# OR_Gate_Using_Transistor.net
KiCad netlist of a schematic drawn in EAGLE
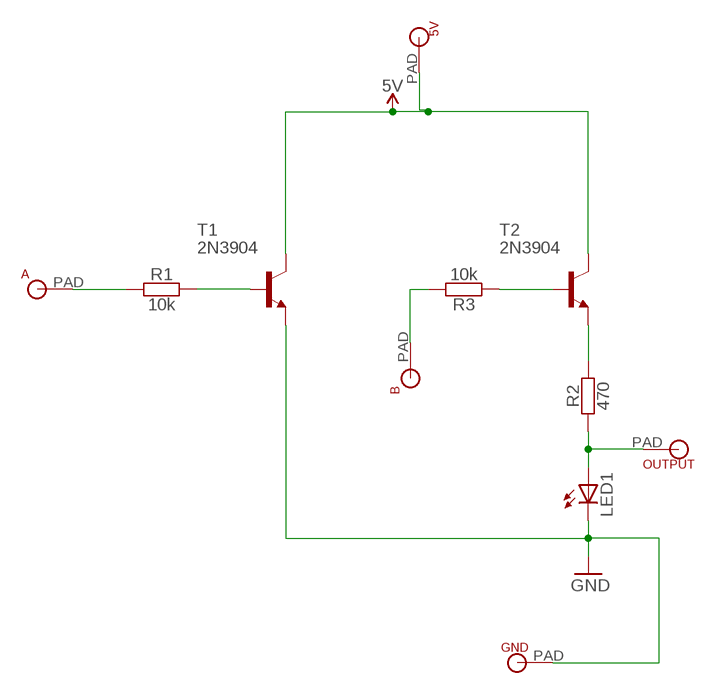
[diagram p0: schematic, sheet 1]

(export (version "E")
  (design (tool "Eeschema 10.0.6"))
  (components
    (comp (ref "5V")
      (value "MICROBIT_PAD")
      (footprint "eagle-import:MICROBIT_PAD")
      (libsource (lib "eagle-import") (part "MICROBIT_PAD"))
    )
    (comp (ref "A")
      (value "MICROBIT_PAD")
      (footprint "eagle-import:MICROBIT_PAD")
      (libsource (lib "eagle-import") (part "MICROBIT_PAD"))
    )
    (comp (ref "B")
      (value "MICROBIT_PAD")
      (footprint "eagle-import:MICROBIT_PAD")
      (libsource (lib "eagle-import") (part "MICROBIT_PAD"))
    )
    (comp (ref "GND")
      (value "MICROBIT_PAD")
      (footprint "eagle-import:MICROBIT_PAD")
      (libsource (lib "eagle-import") (part "MICROBIT_PAD"))
    )
    (comp (ref "LED1")
      (value "LED3MM")
      (footprint "eagle-import:LED3MM")
      (libsource (lib "eagle-import") (part "LED3MM"))
    )
    (comp (ref "OUTPUT")
      (value "MICROBIT_PAD")
      (footprint "eagle-import:MICROBIT_PAD")
      (libsource (lib "eagle-import") (part "MICROBIT_PAD"))
    )
    (comp (ref "R1")
      (value "10k")
      (footprint "eagle-import:R0207_7")
      (libsource (lib "eagle-import") (part "RESISTOR-07"))
    )
    (comp (ref "R2")
      (value "470")
      (footprint "eagle-import:R0207_7")
      (libsource (lib "eagle-import") (part "RESISTOR-07"))
    )
    (comp (ref "R3")
      (value "10k")
      (footprint "eagle-import:R0207_7")
      (libsource (lib "eagle-import") (part "RESISTOR-07"))
    )
    (comp (ref "T1")
      (value "2N3904")
      (footprint "eagle-import:TO92")
      (libsource (lib "eagle-import") (part "2N3904"))
    )
    (comp (ref "T2")
      (value "2N3904")
      (footprint "eagle-import:TO92")
      (libsource (lib "eagle-import") (part "2N3904"))
    )
  )
  (nets
    (net (code "1") (name "5V") (class "Default")
      (node (ref "5V") (pin "PAD") (pinfunction "P$1_PAD") (pintype "bidirectional"))
      (node (ref "T1") (pin "1") (pinfunction "C_1") (pintype "passive"))
      (node (ref "T2") (pin "1") (pinfunction "C_1") (pintype "passive"))
    )
    (net (code "2") (name "GND") (class "Default")
      (node (ref "GND") (pin "PAD") (pinfunction "P$1_PAD") (pintype "bidirectional"))
      (node (ref "LED1") (pin "K") (pinfunction "C_K") (pintype "passive"))
      (node (ref "T1") (pin "3") (pinfunction "E_3") (pintype "passive"))
    )
    (net (code "3") (name "Net-(A-P$1)") (class "Default")
      (node (ref "A") (pin "PAD") (pinfunction "P$1_PAD") (pintype "bidirectional"))
      (node (ref "R1") (pin "1") (pinfunction "1_1") (pintype "passive"))
    )
    (net (code "4") (name "Net-(B-P$1)") (class "Default")
      (node (ref "B") (pin "PAD") (pinfunction "P$1_PAD") (pintype "bidirectional"))
      (node (ref "R3") (pin "2") (pinfunction "2_2") (pintype "passive"))
    )
    (net (code "5") (name "Net-(OUTPUT-P$1)") (class "Default")
      (node (ref "LED1") (pin "A") (pinfunction "A_A") (pintype "passive"))
      (node (ref "OUTPUT") (pin "PAD") (pinfunction "P$1_PAD") (pintype "bidirectional"))
      (node (ref "R2") (pin "1") (pinfunction "1_1") (pintype "passive"))
    )
    (net (code "6") (name "Net-(T1-B)") (class "Default")
      (node (ref "R1") (pin "2") (pinfunction "2_2") (pintype "passive"))
      (node (ref "T1") (pin "2") (pinfunction "B_2") (pintype "passive"))
    )
    (net (code "7") (name "Net-(T2-B)") (class "Default")
      (node (ref "R3") (pin "1") (pinfunction "1_1") (pintype "passive"))
      (node (ref "T2") (pin "2") (pinfunction "B_2") (pintype "passive"))
    )
    (net (code "8") (name "Net-(T2-E)") (class "Default")
      (node (ref "R2") (pin "2") (pinfunction "2_2") (pintype "passive"))
      (node (ref "T2") (pin "3") (pinfunction "E_3") (pintype "passive"))
    )
  )
)
